# 24CXX.net
KiCad netlist of a schematic drawn in Altium Designer
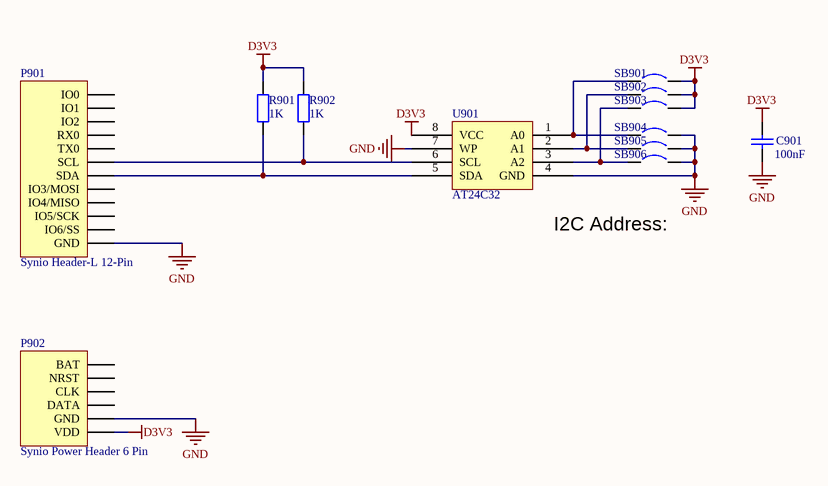
[diagram p0: 24CXX.SchDoc]

(export (version "E")
  (design (tool "Eeschema 10.0.6"))
  (components
    (comp (ref "C901")
      (value "100nF")
      (footprint "0603M")
      (description "Capacitor")
      (fields (field (name "PUBLISHER") "Altium Limited"))
      (libsource (lib "Miscellaneous Devices") (part "Cap"))
    )
    (comp (ref "P901")
      (value "Synio Header-L 12-Pin")
      (footprint "HDR1X12")
      (description "Synio Header-L, 12-Pin")
      (fields (field (name "PUBLISHER") "Altium Limited"))
      (libsource (lib "Connector") (part "Synio Header-L 12-Pin"))
    )
    (comp (ref "P902")
      (value "Synio Power Header 6 Pin")
      (footprint "HDR1X6/2.54MM")
      (libsource (lib "Connector") (part "Synio Power Header 6 Pin"))
    )
    (comp (ref "R901")
      (value "1K")
      (footprint "R0603")
      (description "Resistor")
      (fields (field (name "PUBLISHER") "Altium Limited"))
      (libsource (lib "Miscellaneous Devices") (part "Res2"))
    )
    (comp (ref "R902")
      (value "1K")
      (footprint "R0603")
      (description "Resistor")
      (fields (field (name "PUBLISHER") "Altium Limited"))
      (libsource (lib "Miscellaneous Devices") (part "Res2"))
    )
    (comp (ref "SB901")
      (value "Circuit Breaker")
      (footprint "JP2_SMD")
      (fields (field (name "PUBLISHER") "Altium Limited"))
      (libsource (lib "Misc") (part "Circuit Breaker"))
    )
    (comp (ref "SB902")
      (value "Circuit Breaker")
      (footprint "JP2_SMD")
      (fields (field (name "PUBLISHER") "Altium Limited"))
      (libsource (lib "Misc") (part "Circuit Breaker"))
    )
    (comp (ref "SB903")
      (value "Circuit Breaker")
      (footprint "JP2_SMD")
      (fields (field (name "PUBLISHER") "Altium Limited"))
      (libsource (lib "Misc") (part "Circuit Breaker"))
    )
    (comp (ref "SB904")
      (value "Circuit Breaker")
      (footprint "JP2_SMD")
      (fields (field (name "PUBLISHER") "Altium Limited"))
      (libsource (lib "Misc") (part "Circuit Breaker"))
    )
    (comp (ref "SB905")
      (value "Circuit Breaker")
      (footprint "JP2_SMD")
      (fields (field (name "PUBLISHER") "Altium Limited"))
      (libsource (lib "Misc") (part "Circuit Breaker"))
    )
    (comp (ref "SB906")
      (value "Circuit Breaker")
      (footprint "JP2_SMD")
      (fields (field (name "PUBLISHER") "Altium Limited"))
      (libsource (lib "Misc") (part "Circuit Breaker"))
    )
    (comp (ref "U901")
      (value "AT24C32")
      (footprint "SO8W_M")
      (description "IIC EEPROM")
      (libsource (lib "Logic") (part "At24CXX"))
    )
  )
  (nets
    (net (code "1") (name "D3V3") (class "Default")
      (node (ref "C901") (pin "1") (pinfunction "1_1") (pintype "passive"))
      (node (ref "P902") (pin "1") (pinfunction "VDD_1") (pintype "passive"))
      (node (ref "R901") (pin "2") (pinfunction "2_2") (pintype "passive"))
      (node (ref "R902") (pin "2") (pinfunction "2_2") (pintype "passive"))
      (node (ref "SB901") (pin "2") (pinfunction "2_2") (pintype "passive"))
      (node (ref "SB902") (pin "2") (pinfunction "2_2") (pintype "passive"))
      (node (ref "SB903") (pin "2") (pinfunction "2_2") (pintype "passive"))
      (node (ref "U901") (pin "8") (pinfunction "VCC_8") (pintype "passive"))
    )
    (net (code "2") (name "GND") (class "Default")
      (node (ref "C901") (pin "2") (pinfunction "2_2") (pintype "passive"))
      (node (ref "P901") (pin "1") (pinfunction "GND_1") (pintype "passive"))
      (node (ref "P902") (pin "2") (pinfunction "GND_2") (pintype "passive"))
      (node (ref "SB904") (pin "2") (pinfunction "2_2") (pintype "passive"))
      (node (ref "SB905") (pin "2") (pinfunction "2_2") (pintype "passive"))
      (node (ref "SB906") (pin "2") (pinfunction "2_2") (pintype "passive"))
      (node (ref "U901") (pin "4") (pinfunction "GND_4") (pintype "passive"))
      (node (ref "U901") (pin "7") (pinfunction "WP_7") (pintype "passive"))
    )
    (net (code "3") (name "Net-(P901-SCL)") (class "Default")
      (node (ref "P901") (pin "7") (pinfunction "SCL_7") (pintype "passive"))
      (node (ref "R902") (pin "1") (pinfunction "1_1") (pintype "passive"))
      (node (ref "U901") (pin "6") (pinfunction "SCL_6") (pintype "passive"))
    )
    (net (code "4") (name "Net-(P901-SDA)") (class "Default")
      (node (ref "P901") (pin "6") (pinfunction "SDA_6") (pintype "passive"))
      (node (ref "R901") (pin "1") (pinfunction "1_1") (pintype "passive"))
      (node (ref "U901") (pin "5") (pinfunction "SDA_5") (pintype "passive"))
    )
    (net (code "5") (name "Net-(U901-A0)") (class "Default")
      (node (ref "SB901") (pin "1") (pinfunction "1_1") (pintype "passive"))
      (node (ref "SB904") (pin "1") (pinfunction "1_1") (pintype "passive"))
      (node (ref "U901") (pin "1") (pinfunction "A0_1") (pintype "passive"))
    )
    (net (code "6") (name "Net-(U901-A1)") (class "Default")
      (node (ref "SB902") (pin "1") (pinfunction "1_1") (pintype "passive"))
      (node (ref "SB905") (pin "1") (pinfunction "1_1") (pintype "passive"))
      (node (ref "U901") (pin "2") (pinfunction "A1_2") (pintype "passive"))
    )
    (net (code "7") (name "Net-(U901-A2)") (class "Default")
      (node (ref "SB903") (pin "1") (pinfunction "1_1") (pintype "passive"))
      (node (ref "SB906") (pin "1") (pinfunction "1_1") (pintype "passive"))
      (node (ref "U901") (pin "3") (pinfunction "A2_3") (pintype "passive"))
    )
    (net (code "8") (name "unconnected-(P901-IO0-Pad12)") (class "Default")
      (node (ref "P901") (pin "12") (pinfunction "IO0_12") (pintype "passive"))
    )
    (net (code "9") (name "unconnected-(P901-IO1-Pad11)") (class "Default")
      (node (ref "P901") (pin "11") (pinfunction "IO1_11") (pintype "passive"))
    )
    (net (code "10") (name "unconnected-(P901-IO2-Pad10)") (class "Default")
      (node (ref "P901") (pin "10") (pinfunction "IO2_10") (pintype "passive"))
    )
    (net (code "11") (name "unconnected-(P901-IO3{slash}MOSI-Pad5)") (class "Default")
      (node (ref "P901") (pin "5") (pinfunction "IO3/MOSI_5") (pintype "passive"))
    )
    (net (code "12") (name "unconnected-(P901-IO4{slash}MISO-Pad4)") (class "Default")
      (node (ref "P901") (pin "4") (pinfunction "IO4/MISO_4") (pintype "passive"))
    )
    (net (code "13") (name "unconnected-(P901-IO5{slash}SCK-Pad3)") (class "Default")
      (node (ref "P901") (pin "3") (pinfunction "IO5/SCK_3") (pintype "passive"))
    )
    (net (code "14") (name "unconnected-(P901-IO6{slash}SS-Pad2)") (class "Default")
      (node (ref "P901") (pin "2") (pinfunction "IO6/SS_2") (pintype "passive"))
    )
    (net (code "15") (name "unconnected-(P901-RX0-Pad9)") (class "Default")
      (node (ref "P901") (pin "9") (pinfunction "RX0_9") (pintype "passive"))
    )
    (net (code "16") (name "unconnected-(P901-TX0-Pad8)") (class "Default")
      (node (ref "P901") (pin "8") (pinfunction "TX0_8") (pintype "passive"))
    )
    (net (code "17") (name "unconnected-(P902-BAT-Pad6)") (class "Default")
      (node (ref "P902") (pin "6") (pinfunction "BAT_6") (pintype "passive"))
    )
    (net (code "18") (name "unconnected-(P902-CLK-Pad4)") (class "Default")
      (node (ref "P902") (pin "4") (pinfunction "CLK_4") (pintype "passive"))
    )
    (net (code "19") (name "unconnected-(P902-DATA-Pad3)") (class "Default")
      (node (ref "P902") (pin "3") (pinfunction "DATA_3") (pintype "passive"))
    )
    (net (code "20") (name "unconnected-(P902-NRST-Pad5)") (class "Default")
      (node (ref "P902") (pin "5") (pinfunction "NRST_5") (pintype "passive"))
    )
  )
)
